# Xpt2046.net
KiCad netlist of a schematic drawn in Altium Designer
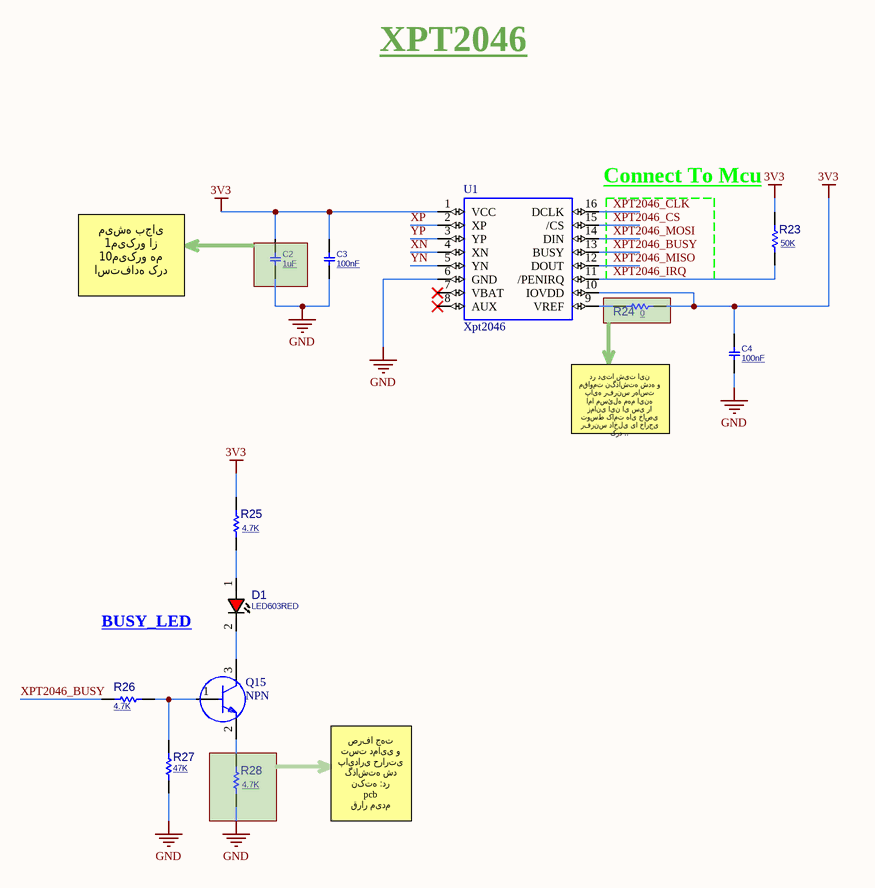
[diagram p0: Xpt2046.SchDoc]

(export (version "E")
  (design (tool "Eeschema 10.0.6"))
  (components
    (comp (ref "C2")
      (value "1uF")
      (footprint "C1206")
      (description "CAP, MLCC, -F, -V, MATERIAL, -%, 0201")
      (fields (field (name "MANF_P#") "MANF_PART#"))
      (libsource (lib "passive_smd") (part "CAP_SMD_MLCC_1206"))
    )
    (comp (ref "C3")
      (value "100nF")
      (footprint "C0603")
      (description "CAP, MLCC, -F, -V, MATERIAL, -%, 0201")
      (fields (field (name "MANF_P#") "MANF_PART#"))
      (libsource (lib "passive_smd") (part "CAP_SMD_MLCC_0603"))
    )
    (comp (ref "C4")
      (value "100nF")
      (footprint "C0603")
      (description "CAP, MLCC, -F, -V, MATERIAL, -%, 0201")
      (fields (field (name "MANF_P#") "MANF_PART#"))
      (libsource (lib "passive_smd") (part "CAP_SMD_MLCC_0603"))
    )
    (comp (ref "D1")
      (value "LED603RED")
      (footprint "LED0603RED")
      (description "LED, SMD, 0603, RED")
      (fields (field (name "MANF") "MANF") (field (name "MANF_P#") "MANF_PART#"))
      (libsource (lib "led(diode)") (part "LED_SMD_0603_RED"))
    )
    (comp (ref "Q15")
      (value "NPN")
      (footprint "FP-SOT23-IPC_A")
      (libsource (lib "NPN-SOT-23") (part "CMP-2000-04931-2"))
    )
    (comp (ref "R23")
      (value "50K")
      (footprint "R0603")
      (description "RESISTOR, SMD")
      (libsource (lib "passive_smd") (part "RES_SMD"))
    )
    (comp (ref "R24")
      (value "0")
      (footprint "R0603")
      (description "RESISTOR, SMD")
      (libsource (lib "passive_smd") (part "RES_SMD"))
    )
    (comp (ref "R25")
      (value "4.7K")
      (footprint "R0603")
      (description "RESISTOR, SMD")
      (libsource (lib "passive_smd") (part "RES_SMD"))
    )
    (comp (ref "R26")
      (value "4.7K")
      (footprint "R0603")
      (description "RESISTOR, SMD")
      (libsource (lib "passive_smd") (part "RES_SMD"))
    )
    (comp (ref "R27")
      (value "47K")
      (footprint "R0603")
      (description "RESISTOR, SMD")
      (libsource (lib "passive_smd") (part "RES_SMD"))
    )
    (comp (ref "R28")
      (value "4.7K")
      (footprint "R0603")
      (description "RESISTOR, SMD")
      (libsource (lib "passive_smd") (part "RES_SMD"))
    )
    (comp (ref "U1") (value "Xpt2046") (footprint "Xpt2046") (libsource (lib "XPT2046") (part "Xpt2046")))
  )
  (nets
    (net (code "1") (name "/XN") (class "Default")
      (node (ref "U1") (pin "4") (pinfunction "XN_4") (pintype "bidirectional"))
    )
    (net (code "2") (name "/XP") (class "Default")
      (node (ref "U1") (pin "2") (pinfunction "XP_2") (pintype "bidirectional"))
    )
    (net (code "3") (name "/XPT2046_BUSY") (class "Default")
      (node (ref "R26") (pin "2") (pinfunction "2_2") (pintype "passive"))
      (node (ref "U1") (pin "13") (pinfunction "BUSY_13") (pintype "bidirectional"))
    )
    (net (code "4") (name "/XPT2046_CLK") (class "Default")
      (node (ref "U1") (pin "16") (pinfunction "DCLK_16") (pintype "bidirectional"))
    )
    (net (code "5") (name "/XPT2046_CS") (class "Default")
      (node (ref "U1") (pin "15") (pinfunction "/CS_15") (pintype "bidirectional"))
    )
    (net (code "6") (name "/XPT2046_IRQ") (class "Default")
      (node (ref "R23") (pin "1") (pinfunction "1_1") (pintype "passive"))
      (node (ref "U1") (pin "11") (pinfunction "/PENIRQ_11") (pintype "bidirectional"))
    )
    (net (code "7") (name "/XPT2046_MISO") (class "Default")
      (node (ref "U1") (pin "12") (pinfunction "DOUT_12") (pintype "bidirectional"))
    )
    (net (code "8") (name "/XPT2046_MOSI") (class "Default")
      (node (ref "U1") (pin "14") (pinfunction "DIN_14") (pintype "bidirectional"))
    )
    (net (code "9") (name "/YN") (class "Default")
      (node (ref "U1") (pin "5") (pinfunction "YN_5") (pintype "bidirectional"))
    )
    (net (code "10") (name "/YP") (class "Default")
      (node (ref "U1") (pin "3") (pinfunction "YP_3") (pintype "bidirectional"))
    )
    (net (code "11") (name "3V3") (class "Default")
      (node (ref "C2") (pin "2") (pinfunction "2_2") (pintype "passive"))
      (node (ref "C3") (pin "2") (pinfunction "2_2") (pintype "passive"))
      (node (ref "C4") (pin "2") (pinfunction "2_2") (pintype "passive"))
      (node (ref "R23") (pin "2") (pinfunction "2_2") (pintype "passive"))
      (node (ref "R24") (pin "1") (pinfunction "1_1") (pintype "passive"))
      (node (ref "R25") (pin "2") (pinfunction "2_2") (pintype "passive"))
      (node (ref "U1") (pin "1") (pinfunction "VCC_1") (pintype "bidirectional"))
      (node (ref "U1") (pin "10") (pinfunction "IOVDD_10") (pintype "bidirectional"))
    )
    (net (code "12") (name "GND") (class "Default")
      (node (ref "C2") (pin "1") (pinfunction "1_1") (pintype "passive"))
      (node (ref "C3") (pin "1") (pinfunction "1_1") (pintype "passive"))
      (node (ref "C4") (pin "1") (pinfunction "1_1") (pintype "passive"))
      (node (ref "R27") (pin "2") (pinfunction "2_2") (pintype "passive"))
      (node (ref "R28") (pin "1") (pinfunction "1_1") (pintype "passive"))
      (node (ref "U1") (pin "6") (pinfunction "GND_6") (pintype "bidirectional"))
    )
    (net (code "13") (name "Net-(D1-ANODE)") (class "Default")
      (node (ref "D1") (pin "1") (pinfunction "ANODE_1") (pintype "passive"))
      (node (ref "R25") (pin "1") (pinfunction "1_1") (pintype "passive"))
    )
    (net (code "14") (name "Net-(D1-CATHODE)") (class "Default")
      (node (ref "D1") (pin "2") (pinfunction "CATHODE_2") (pintype "passive"))
      (node (ref "Q15") (pin "3") (pinfunction "C_3") (pintype "passive"))
    )
    (net (code "15") (name "Net-(Q15-B)") (class "Default")
      (node (ref "Q15") (pin "1") (pinfunction "B_1") (pintype "passive"))
      (node (ref "R26") (pin "1") (pinfunction "1_1") (pintype "passive"))
      (node (ref "R27") (pin "1") (pinfunction "1_1") (pintype "passive"))
    )
    (net (code "16") (name "Net-(Q15-E)") (class "Default")
      (node (ref "Q15") (pin "2") (pinfunction "E_2") (pintype "passive"))
      (node (ref "R28") (pin "2") (pinfunction "2_2") (pintype "passive"))
    )
    (net (code "17") (name "Net-(U1-VREF)") (class "Default")
      (node (ref "R24") (pin "2") (pinfunction "2_2") (pintype "passive"))
      (node (ref "U1") (pin "9") (pinfunction "VREF_9") (pintype "bidirectional"))
    )
    (net (code "18") (name "unconnected-(U1-AUX-Pad8)") (class "Default")
      (node (ref "U1") (pin "8") (pinfunction "AUX_8") (pintype "bidirectional+no_connect"))
    )
    (net (code "19") (name "unconnected-(U1-VBAT-Pad7)") (class "Default")
      (node (ref "U1") (pin "7") (pinfunction "VBAT_7") (pintype "bidirectional+no_connect"))
    )
  )
)
